# TalkingTrain.net
KiCad netlist of a schematic drawn in EasyEDA Pro
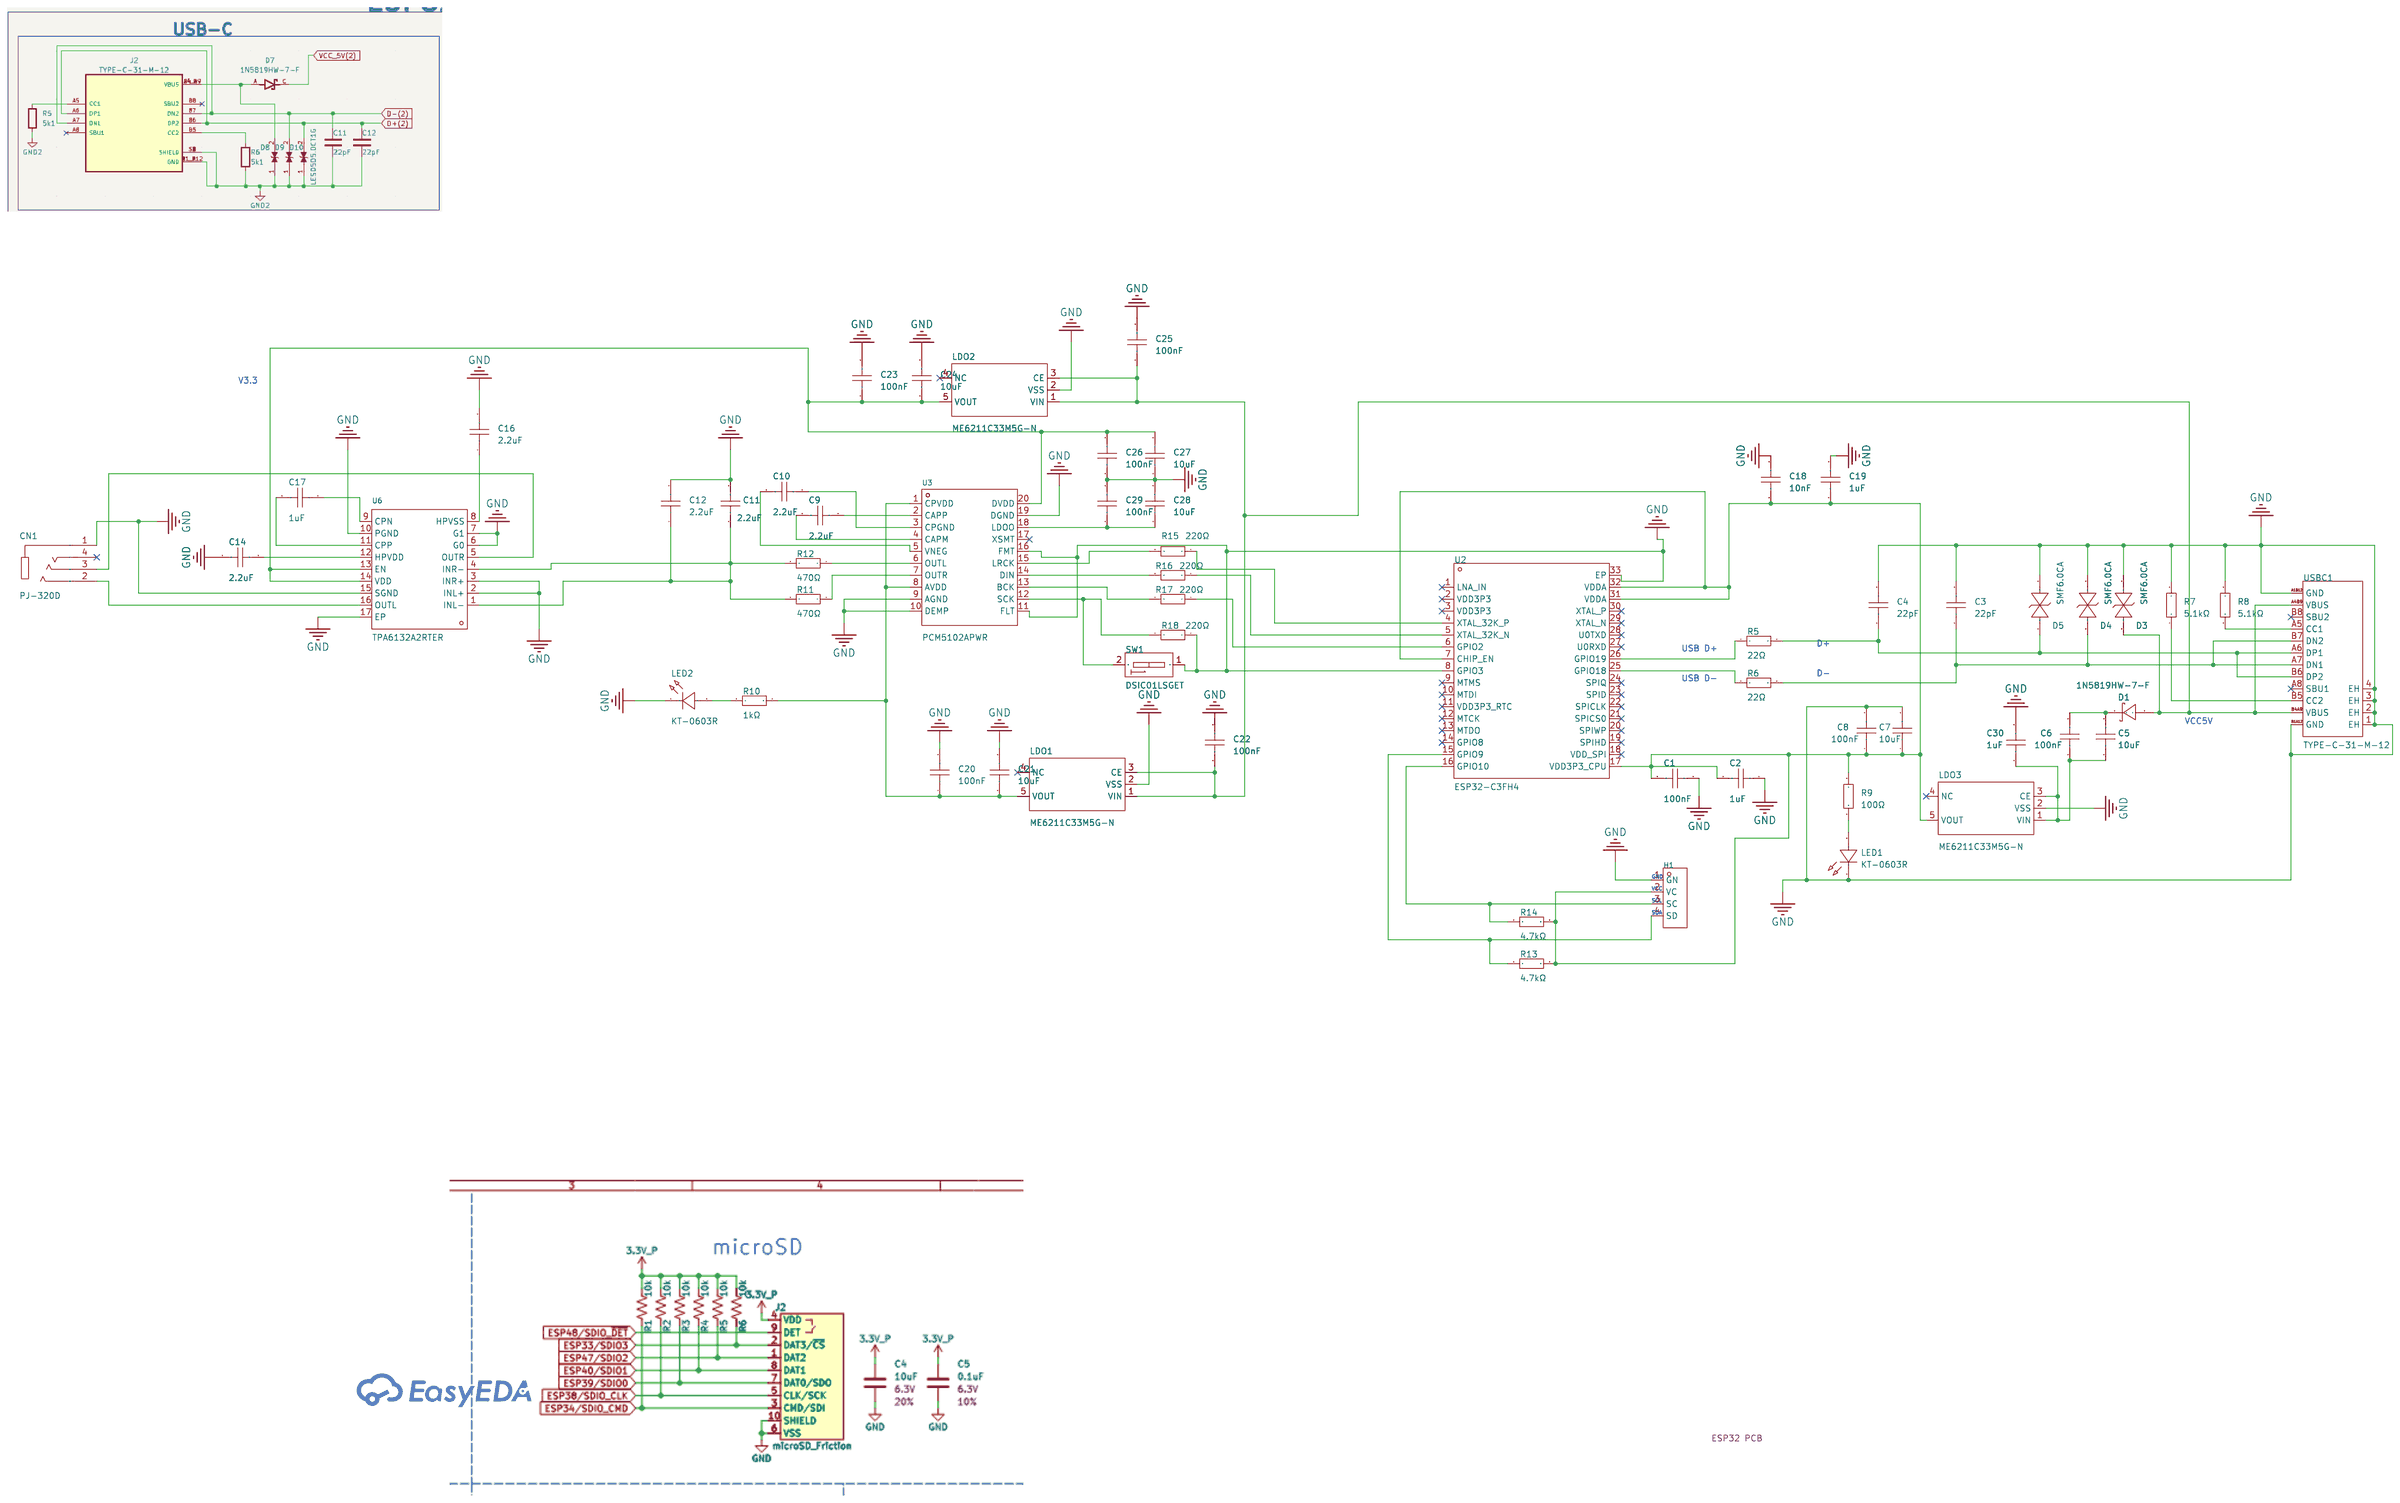
[diagram p0: schematic sheet]

(export (version "E")
  (design (tool "Eeschema 10.0.6"))
  (components
    (comp (ref "C1")
      (value "100nF")
      (footprint "easyedapro:C0603")
      (description "Capacitance:100nF Tolerance:±10% Tolerance:±10% Voltage Rating:50V Temperature Coefficient:X7R")
      (fields
        (field (name "Manufacturer Part") "CC0603KRX7R9BB104")
        (field (name "Manufacturer") "YAGEO(国巨)")
      )
      (libsource (lib "easyedapro") (part "CAP"))
    )
    (comp (ref "C2")
      (value "1uF")
      (footprint "easyedapro:C0603")
      (description "Capacitance:1uF Tolerance:±10% Tolerance:±10% Voltage Rating:50V Temperature Coefficient:X5R")
      (fields
        (field (name "Manufacturer Part") "CL10A105KB8NNNC")
        (field (name "Manufacturer") "SAMSUNG(三星)")
      )
      (libsource (lib "easyedapro") (part "CAP"))
    )
    (comp (ref "C3")
      (value "22pF")
      (footprint "easyedapro:C0603")
      (description "Capacitance:22pF Tolerance:±5% Tolerance:±5% Voltage Rating:50V Temperature Coefficient:C0G")
      (fields
        (field (name "Manufacturer Part") "CL10C220JB8NNNC")
        (field (name "Manufacturer") "SAMSUNG(三星)")
      )
      (libsource (lib "easyedapro") (part "CAP"))
    )
    (comp (ref "C4")
      (value "22pF")
      (footprint "easyedapro:C0603")
      (description "Capacitance:22pF Tolerance:±5% Tolerance:±5% Voltage Rating:50V Temperature Coefficient:C0G")
      (fields
        (field (name "Manufacturer Part") "CL10C220JB8NNNC")
        (field (name "Manufacturer") "SAMSUNG(三星)")
      )
      (libsource (lib "easyedapro") (part "CAP"))
    )
    (comp (ref "C5")
      (value "10uF")
      (footprint "easyedapro:C0603")
      (description "Capacitance:10uF Tolerance:±10% Tolerance:±10% Voltage Rating:10V Temperature Coefficient:X5R")
      (fields
        (field (name "Manufacturer Part") "CL10A106KP8NNNC")
        (field (name "Manufacturer") "SAMSUNG(三星)")
      )
      (libsource (lib "easyedapro") (part "CAP"))
    )
    (comp (ref "C6")
      (value "100nF")
      (footprint "easyedapro:C0603")
      (description "Capacitance:100nF Tolerance:±10% Tolerance:±10% Voltage Rating:50V Temperature Coefficient:X7R")
      (fields
        (field (name "Manufacturer Part") "CC0603KRX7R9BB104")
        (field (name "Manufacturer") "YAGEO(国巨)")
      )
      (libsource (lib "easyedapro") (part "CAP"))
    )
    (comp (ref "C7")
      (value "10uF")
      (footprint "easyedapro:C0603")
      (description "Capacitance:10uF Tolerance:±10% Tolerance:±10% Voltage Rating:10V Temperature Coefficient:X5R")
      (fields
        (field (name "Manufacturer Part") "CL10A106KP8NNNC")
        (field (name "Manufacturer") "SAMSUNG(三星)")
      )
      (libsource (lib "easyedapro") (part "CAP"))
    )
    (comp (ref "C8")
      (value "100nF")
      (footprint "easyedapro:C0603")
      (description "Capacitance:100nF Tolerance:±10% Tolerance:±10% Voltage Rating:50V Temperature Coefficient:X7R")
      (fields
        (field (name "Manufacturer Part") "CC0603KRX7R9BB104")
        (field (name "Manufacturer") "YAGEO(国巨)")
      )
      (libsource (lib "easyedapro") (part "CAP"))
    )
    (comp (ref "C9")
      (value "2.2uF")
      (footprint "easyedapro:C0603")
      (description "Capacitance:2.2uF Tolerance:±10% Tolerance:±10% Voltage Rating:16V Temperature Coefficient:X5R")
      (fields
        (field (name "Manufacturer Part") "CL10A225KO8NNNC")
        (field (name "Manufacturer") "SAMSUNG(三星)")
      )
      (libsource (lib "easyedapro") (part "CAP"))
    )
    (comp (ref "C10")
      (value "2.2uF")
      (footprint "easyedapro:C0603")
      (description "Capacitance:2.2uF Tolerance:±10% Tolerance:±10% Voltage Rating:16V Temperature Coefficient:X5R")
      (fields
        (field (name "Manufacturer Part") "CL10A225KO8NNNC")
        (field (name "Manufacturer") "SAMSUNG(三星)")
      )
      (libsource (lib "easyedapro") (part "CAP"))
    )
    (comp (ref "C11")
      (value "2.2uF")
      (footprint "easyedapro:C0603")
      (description "Capacitance:2.2uF Tolerance:±10% Tolerance:±10% Voltage Rating:16V Temperature Coefficient:X5R")
      (fields
        (field (name "Manufacturer Part") "CL10A225KO8NNNC")
        (field (name "Manufacturer") "SAMSUNG(三星)")
      )
      (libsource (lib "easyedapro") (part "CAP"))
    )
    (comp (ref "C12")
      (value "2.2uF")
      (footprint "easyedapro:C0603")
      (description "Capacitance:2.2uF Tolerance:±10% Tolerance:±10% Voltage Rating:16V Temperature Coefficient:X5R")
      (fields
        (field (name "Manufacturer Part") "CL10A225KO8NNNC")
        (field (name "Manufacturer") "SAMSUNG(三星)")
      )
      (libsource (lib "easyedapro") (part "CAP"))
    )
    (comp (ref "C14")
      (value "2.2uF")
      (footprint "easyedapro:C0603")
      (description "Capacitance:2.2uF Tolerance:±10% Tolerance:±10% Voltage Rating:16V Temperature Coefficient:X5R")
      (fields
        (field (name "Manufacturer Part") "CL10A225KO8NNNC")
        (field (name "Manufacturer") "SAMSUNG(三星)")
      )
      (libsource (lib "easyedapro") (part "CAP"))
    )
    (comp (ref "C16")
      (value "2.2uF")
      (footprint "easyedapro:C0603")
      (description "Capacitance:2.2uF Tolerance:±10% Tolerance:±10% Voltage Rating:16V Temperature Coefficient:X5R")
      (fields
        (field (name "Manufacturer Part") "CL10A225KO8NNNC")
        (field (name "Manufacturer") "SAMSUNG(三星)")
      )
      (libsource (lib "easyedapro") (part "CAP"))
    )
    (comp (ref "C17")
      (value "1uF")
      (footprint "easyedapro:C0603")
      (description "Capacitance:1uF Tolerance:±10% Tolerance:±10% Voltage Rating:50V Temperature Coefficient:X5R")
      (fields
        (field (name "Manufacturer Part") "CL10A105KB8NNNC")
        (field (name "Manufacturer") "SAMSUNG(三星)")
      )
      (libsource (lib "easyedapro") (part "CAP"))
    )
    (comp (ref "C18")
      (value "10nF")
      (footprint "easyedapro:C0603")
      (description "Capacitance:10nF Tolerance:±10% Tolerance:±10% Voltage Rating:50V Temperature Coefficient:X7R")
      (fields (field (name "Manufacturer Part") "0603B103K500NT") (field (name "Manufacturer") "FH(风华)"))
      (libsource (lib "easyedapro") (part "CAP"))
    )
    (comp (ref "C19")
      (value "1uF")
      (footprint "easyedapro:C0603")
      (description "Capacitance:1uF Tolerance:±10% Tolerance:±10% Voltage Rating:50V Temperature Coefficient:X5R")
      (fields
        (field (name "Manufacturer Part") "CL10A105KB8NNNC")
        (field (name "Manufacturer") "SAMSUNG(三星)")
      )
      (libsource (lib "easyedapro") (part "CAP"))
    )
    (comp (ref "C20")
      (value "100nF")
      (footprint "easyedapro:C0603")
      (description "Capacitance:100nF Tolerance:±10% Tolerance:±10% Voltage Rating:50V Temperature Coefficient:X7R")
      (fields
        (field (name "Manufacturer Part") "CC0603KRX7R9BB104")
        (field (name "Manufacturer") "YAGEO(国巨)")
      )
      (libsource (lib "easyedapro") (part "CAP"))
    )
    (comp (ref "C21")
      (value "10uF")
      (footprint "easyedapro:C0603")
      (description "Capacitance:10uF Tolerance:±10% Tolerance:±10% Voltage Rating:10V Temperature Coefficient:X5R")
      (fields
        (field (name "Manufacturer Part") "CL10A106KP8NNNC")
        (field (name "Manufacturer") "SAMSUNG(三星)")
      )
      (libsource (lib "easyedapro") (part "CAP"))
    )
    (comp (ref "C22")
      (value "100nF")
      (footprint "easyedapro:C0603")
      (description "Capacitance:100nF Tolerance:±10% Tolerance:±10% Voltage Rating:50V Temperature Coefficient:X7R")
      (fields
        (field (name "Manufacturer Part") "CC0603KRX7R9BB104")
        (field (name "Manufacturer") "YAGEO(国巨)")
      )
      (libsource (lib "easyedapro") (part "CAP"))
    )
    (comp (ref "C23")
      (value "100nF")
      (footprint "easyedapro:C0603")
      (description "Capacitance:100nF Tolerance:±10% Tolerance:±10% Voltage Rating:50V Temperature Coefficient:X7R")
      (fields
        (field (name "Manufacturer Part") "CC0603KRX7R9BB104")
        (field (name "Manufacturer") "YAGEO(国巨)")
      )
      (libsource (lib "easyedapro") (part "CAP"))
    )
    (comp (ref "C24")
      (value "10uF")
      (footprint "easyedapro:C0603")
      (description "Capacitance:10uF Tolerance:±10% Tolerance:±10% Voltage Rating:10V Temperature Coefficient:X5R")
      (fields
        (field (name "Manufacturer Part") "CL10A106KP8NNNC")
        (field (name "Manufacturer") "SAMSUNG(三星)")
      )
      (libsource (lib "easyedapro") (part "CAP"))
    )
    (comp (ref "C25")
      (value "100nF")
      (footprint "easyedapro:C0603")
      (description "Capacitance:100nF Tolerance:±10% Tolerance:±10% Voltage Rating:50V Temperature Coefficient:X7R")
      (fields
        (field (name "Manufacturer Part") "CC0603KRX7R9BB104")
        (field (name "Manufacturer") "YAGEO(国巨)")
      )
      (libsource (lib "easyedapro") (part "CAP"))
    )
    (comp (ref "C26")
      (value "100nF")
      (footprint "easyedapro:C0603")
      (description "Capacitance:100nF Tolerance:±10% Tolerance:±10% Voltage Rating:50V Temperature Coefficient:X7R")
      (fields
        (field (name "Manufacturer Part") "CC0603KRX7R9BB104")
        (field (name "Manufacturer") "YAGEO(国巨)")
      )
      (libsource (lib "easyedapro") (part "CAP"))
    )
    (comp (ref "C27")
      (value "10uF")
      (footprint "easyedapro:C0603")
      (description "Capacitance:10uF Tolerance:±10% Tolerance:±10% Voltage Rating:10V Temperature Coefficient:X5R")
      (fields
        (field (name "Manufacturer Part") "CL10A106KP8NNNC")
        (field (name "Manufacturer") "SAMSUNG(三星)")
      )
      (libsource (lib "easyedapro") (part "CAP"))
    )
    (comp (ref "C28")
      (value "10uF")
      (footprint "easyedapro:C0603")
      (description "Capacitance:10uF Tolerance:±10% Tolerance:±10% Voltage Rating:10V Temperature Coefficient:X5R")
      (fields
        (field (name "Manufacturer Part") "CL10A106KP8NNNC")
        (field (name "Manufacturer") "SAMSUNG(三星)")
      )
      (libsource (lib "easyedapro") (part "CAP"))
    )
    (comp (ref "C29")
      (value "100nF")
      (footprint "easyedapro:C0603")
      (description "Capacitance:100nF Tolerance:±10% Tolerance:±10% Voltage Rating:50V Temperature Coefficient:X7R")
      (fields
        (field (name "Manufacturer Part") "CC0603KRX7R9BB104")
        (field (name "Manufacturer") "YAGEO(国巨)")
      )
      (libsource (lib "easyedapro") (part "CAP"))
    )
    (comp (ref "C30")
      (value "1uF")
      (footprint "easyedapro:C0603")
      (description "Capacitance:1uF Tolerance:±10% Tolerance:±10% Voltage Rating:50V Temperature Coefficient:X7R")
      (fields
        (field (name "Manufacturer Part") "CL31B105KBHNNNE")
        (field (name "Manufacturer") "SAMSUNG(三星)")
      )
      (libsource (lib "easyedapro") (part "CAP"))
    )
    (comp (ref "CN1")
      (value "PJ-320D")
      (footprint "easyedapro:AUDIO-SMD_PJ-320D-1")
      (fields (field (name "Manufacturer") "SHOU HAN(首韩)"))
      (libsource (lib "easyedapro") (part "PJ-320D"))
    )
    (comp (ref "D1")
      (value "1N5819HW-7-F")
      (footprint "easyedapro:SOD-123_L2.7-W1.6-LS3.7-RD")
      (fields (field (name "Manufacturer") "DIODES(美台)"))
      (libsource (lib "easyedapro") (part "1N5819HW-7-F"))
    )
    (comp (ref "D3")
      (value "SMF6.0CA")
      (footprint "easyedapro:SOD-123FL_L2.7-W1.8-LS3.8-BI")
      (fields (field (name "Manufacturer") "R+O(宏嘉诚)"))
      (libsource (lib "easyedapro") (part "SMF6.0CA_C19077500"))
    )
    (comp (ref "D4")
      (value "SMF6.0CA")
      (footprint "easyedapro:SOD-123FL_L2.7-W1.8-LS3.8-BI")
      (fields (field (name "Manufacturer") "R+O(宏嘉诚)"))
      (libsource (lib "easyedapro") (part "SMF6.0CA_C19077500"))
    )
    (comp (ref "D5")
      (value "SMF6.0CA")
      (footprint "easyedapro:SOD-123FL_L2.7-W1.8-LS3.8-BI")
      (fields (field (name "Manufacturer") "R+O(宏嘉诚)"))
      (libsource (lib "easyedapro") (part "SMF6.0CA_C19077500"))
    )
    (comp (ref "H1")
      (value "2.54-1*4P母")
      (footprint "easyedapro:HDR-TH_4P-P2.54-V-F")
      (fields (field (name "Manufacturer") "BOOMELE(博穆精密)"))
      (libsource (lib "easyedapro") (part "2.54-1*4P母"))
    )
    (comp (ref "LDO1")
      (value "ME6211C33M5G-N")
      (footprint "easyedapro:SOT-23-5_L3.0-W1.7-P0.95-LS2.8-BL")
      (fields (field (name "Manufacturer") "MICRONE(南京微盟)"))
      (libsource (lib "easyedapro") (part "ME6211C33M5G-N"))
    )
    (comp (ref "LDO2")
      (value "ME6211C33M5G-N")
      (footprint "easyedapro:SOT-23-5_L3.0-W1.7-P0.95-LS2.8-BL")
      (fields (field (name "Manufacturer") "MICRONE(南京微盟)"))
      (libsource (lib "easyedapro") (part "ME6211C33M5G-N"))
    )
    (comp (ref "LDO3")
      (value "ME6211C33M5G-N")
      (footprint "easyedapro:SOT-23-5_L3.0-W1.7-P0.95-LS2.8-BL")
      (fields (field (name "Manufacturer") "MICRONE(南京微盟)"))
      (libsource (lib "easyedapro") (part "ME6211C33M5G-N"))
    )
    (comp (ref "LED1")
      (value "KT-0603R")
      (footprint "easyedapro:LED0603-RD_RED")
      (fields (field (name "Manufacturer") "KENTO"))
      (libsource (lib "easyedapro") (part "XL-1608SURC-06"))
    )
    (comp (ref "LED2")
      (value "KT-0603R")
      (footprint "easyedapro:LED0603-RD_RED")
      (fields (field (name "Manufacturer") "KENTO"))
      (libsource (lib "easyedapro") (part "XL-1608SURC-06"))
    )
    (comp (ref "R5")
      (value "22Ω")
      (footprint "easyedapro:R0603")
      (fields
        (field (name "Manufacturer Part") "0603WAF220JT5E")
        (field (name "Manufacturer") "UNI-ROYAL(厚声)")
      )
      (libsource (lib "easyedapro") (part "Res"))
    )
    (comp (ref "R6")
      (value "22Ω")
      (footprint "easyedapro:R0603")
      (fields
        (field (name "Manufacturer Part") "0603WAF220JT5E")
        (field (name "Manufacturer") "UNI-ROYAL(厚声)")
      )
      (libsource (lib "easyedapro") (part "Res"))
    )
    (comp (ref "R7")
      (value "5.1kΩ")
      (footprint "easyedapro:R0603")
      (fields
        (field (name "Manufacturer Part") "0805W8F5101T5E")
        (field (name "Manufacturer") "UNI-ROYAL(厚声)")
      )
      (libsource (lib "easyedapro") (part "Res"))
    )
    (comp (ref "R8")
      (value "5.1kΩ")
      (footprint "easyedapro:R0603")
      (fields
        (field (name "Manufacturer Part") "0805W8F5101T5E")
        (field (name "Manufacturer") "UNI-ROYAL(厚声)")
      )
      (libsource (lib "easyedapro") (part "Res"))
    )
    (comp (ref "R9")
      (value "100Ω")
      (footprint "easyedapro:R0603")
      (fields
        (field (name "Manufacturer Part") "0603WAF1000T5E")
        (field (name "Manufacturer") "UNI-ROYAL(厚声)")
      )
      (libsource (lib "easyedapro") (part "Res"))
    )
    (comp (ref "R10")
      (value "1kΩ")
      (footprint "easyedapro:R0603")
      (fields
        (field (name "Manufacturer Part") "0603WAF1001T5E")
        (field (name "Manufacturer") "UNI-ROYAL(厚声)")
      )
      (libsource (lib "easyedapro") (part "Res"))
    )
    (comp (ref "R11")
      (value "470Ω")
      (footprint "easyedapro:R0603")
      (fields
        (field (name "Manufacturer Part") "0603WAF4700T5E")
        (field (name "Manufacturer") "UNI-ROYAL(厚声)")
      )
      (libsource (lib "easyedapro") (part "Res"))
    )
    (comp (ref "R12")
      (value "470Ω")
      (footprint "easyedapro:R0603")
      (fields
        (field (name "Manufacturer Part") "0603WAF4700T5E")
        (field (name "Manufacturer") "UNI-ROYAL(厚声)")
      )
      (libsource (lib "easyedapro") (part "Res"))
    )
    (comp (ref "R13")
      (value "4.7kΩ")
      (footprint "easyedapro:R0603")
      (fields
        (field (name "Manufacturer Part") "0603WAF4701T5E")
        (field (name "Manufacturer") "UNI-ROYAL(厚声)")
      )
      (libsource (lib "easyedapro") (part "Res"))
    )
    (comp (ref "R14")
      (value "4.7kΩ")
      (footprint "easyedapro:R0603")
      (fields
        (field (name "Manufacturer Part") "0603WAF4701T5E")
        (field (name "Manufacturer") "UNI-ROYAL(厚声)")
      )
      (libsource (lib "easyedapro") (part "Res"))
    )
    (comp (ref "R15")
      (value "220Ω")
      (footprint "easyedapro:R0603")
      (fields
        (field (name "Manufacturer Part") "0603WAF2200T5E")
        (field (name "Manufacturer") "UNI-ROYAL(厚声)")
      )
      (libsource (lib "easyedapro") (part "Res"))
    )
    (comp (ref "R16")
      (value "220Ω")
      (footprint "easyedapro:R0603")
      (fields
        (field (name "Manufacturer Part") "0603WAF2200T5E")
        (field (name "Manufacturer") "UNI-ROYAL(厚声)")
      )
      (libsource (lib "easyedapro") (part "Res"))
    )
    (comp (ref "R17")
      (value "220Ω")
      (footprint "easyedapro:R0603")
      (fields
        (field (name "Manufacturer Part") "0603WAF2200T5E")
        (field (name "Manufacturer") "UNI-ROYAL(厚声)")
      )
      (libsource (lib "easyedapro") (part "Res"))
    )
    (comp (ref "R18")
      (value "220Ω")
      (footprint "easyedapro:R0603")
      (fields
        (field (name "Manufacturer Part") "0603WAF2200T5E")
        (field (name "Manufacturer") "UNI-ROYAL(厚声)")
      )
      (libsource (lib "easyedapro") (part "Res"))
    )
    (comp (ref "SW1")
      (value "DSIC01LSGET")
      (footprint "easyedapro:SW-SMD_DSIC01LSGET")
      (description "Type:Slide, Rocked Circuit:SPST Number of Positions:1 Lead Pitch:- Operating Life:- Color:Black")
      (fields (field (name "Manufacturer") "YE"))
      (libsource (lib "easyedapro") (part "DSIC01LSGET"))
    )
    (comp (ref "U2")
      (value "ESP32-C3FH4")
      (footprint "easyedapro:QFN-32_L5.0-W5.0-P0.50-TL-EP3.7")
      (fields (field (name "Manufacturer") "ESPRESSIF(乐鑫)"))
      (libsource (lib "easyedapro") (part "ESP32-C3FH4"))
    )
    (comp (ref "U3")
      (value "PCM5102APWR")
      (footprint "easyedapro:TSSOP-20_L6.5-W4.4-P0.65-LS6.4-BL")
      (fields (field (name "Manufacturer") "TI(德州仪器)"))
      (libsource (lib "easyedapro") (part "PCM5102APWR"))
    )
    (comp (ref "U6")
      (value "TPA6132A2RTER")
      (footprint "easyedapro:WQFN-16_L3.0-W3.0-P0.50-TL-EP1.6")
      (fields (field (name "Manufacturer") "TI(德州仪器)"))
      (libsource (lib "easyedapro") (part "TPA6132A2RTER"))
    )
    (comp (ref "USBC1")
      (value "TYPE-C-31-M-12")
      (footprint "easyedapro:USB-C_SMD-TYPE-C-31-M-12_1")
      (fields (field (name "Manufacturer") "韩国韩荣"))
      (libsource (lib "easyedapro") (part "TYPE-C-31-M-12"))
    )
  )
  (nets
    (net (code "1") (name "GND") (class "Default")
      (node (ref "C1") (pin "1") (pinfunction "1_1") (pintype "input"))
      (node (ref "C11") (pin "2") (pinfunction "2_2") (pintype "input"))
      (node (ref "C12") (pin "2") (pinfunction "2_2") (pintype "input"))
      (node (ref "C14") (pin "1") (pinfunction "1_1") (pintype "input"))
      (node (ref "C16") (pin "2") (pinfunction "2_2") (pintype "input"))
      (node (ref "C18") (pin "1") (pinfunction "1_1") (pintype "input"))
      (node (ref "C19") (pin "1") (pinfunction "1_1") (pintype "input"))
      (node (ref "C2") (pin "1") (pinfunction "1_1") (pintype "input"))
      (node (ref "C20") (pin "2") (pinfunction "2_2") (pintype "input"))
      (node (ref "C21") (pin "2") (pinfunction "2_2") (pintype "input"))
      (node (ref "C22") (pin "2") (pinfunction "2_2") (pintype "input"))
      (node (ref "C23") (pin "2") (pinfunction "2_2") (pintype "input"))
      (node (ref "C24") (pin "2") (pinfunction "2_2") (pintype "input"))
      (node (ref "C25") (pin "2") (pinfunction "2_2") (pintype "input"))
      (node (ref "C26") (pin "1") (pinfunction "1_1") (pintype "input"))
      (node (ref "C27") (pin "1") (pinfunction "1_1") (pintype "input"))
      (node (ref "C28") (pin "2") (pinfunction "2_2") (pintype "input"))
      (node (ref "C29") (pin "2") (pinfunction "2_2") (pintype "input"))
      (node (ref "C3") (pin "2") (pinfunction "2_2") (pintype "input"))
      (node (ref "C30") (pin "2") (pinfunction "2_2") (pintype "input"))
      (node (ref "C4") (pin "2") (pinfunction "2_2") (pintype "input"))
      (node (ref "C7") (pin "2") (pinfunction "2_2") (pintype "input"))
      (node (ref "C8") (pin "2") (pinfunction "2_2") (pintype "input"))
      (node (ref "CN1") (pin "1") (pinfunction "1_1") (pintype "unspecified"))
      (node (ref "D3") (pin "1") (pinfunction "1_1") (pintype "unspecified"))
      (node (ref "D4") (pin "1") (pinfunction "1_1") (pintype "unspecified"))
      (node (ref "D5") (pin "1") (pinfunction "1_1") (pintype "unspecified"))
      (node (ref "H1") (pin "1") (pinfunction "GN_1") (pintype "input"))
      (node (ref "LDO1") (pin "2") (pinfunction "VSS_2") (pintype "unspecified"))
      (node (ref "LDO2") (pin "2") (pinfunction "VSS_2") (pintype "unspecified"))
      (node (ref "LDO3") (pin "2") (pinfunction "VSS_2") (pintype "unspecified"))
      (node (ref "LED1") (pin "1") (pinfunction "K_1") (pintype "unspecified"))
      (node (ref "LED2") (pin "1") (pinfunction "K_1") (pintype "unspecified"))
      (node (ref "R18") (pin "1") (pinfunction "1_1") (pintype "input"))
      (node (ref "R7") (pin "2") (pinfunction "2_2") (pintype "input"))
      (node (ref "R8") (pin "2") (pinfunction "2_2") (pintype "input"))
      (node (ref "SW1") (pin "1") (pinfunction "A1_1") (pintype "input"))
      (node (ref "U2") (pin "33") (pinfunction "EP_33") (pintype "unspecified"))
      (node (ref "U2") (pin "8") (pinfunction "GPIO3_8") (pintype "unspecified"))
      (node (ref "U3") (pin "10") (pinfunction "DEMP_10") (pintype "input"))
      (node (ref "U3") (pin "11") (pinfunction "FLT_11") (pintype "input"))
      (node (ref "U3") (pin "16") (pinfunction "FMT_16") (pintype "input"))
      (node (ref "U3") (pin "19") (pinfunction "DGND_19") (pintype "input"))
      (node (ref "U3") (pin "9") (pinfunction "AGND_9") (pintype "input"))
      (node (ref "U6") (pin "10") (pinfunction "PGND_10") (pintype "input"))
      (node (ref "U6") (pin "15") (pinfunction "SGND_15") (pintype "input"))
      (node (ref "U6") (pin "17") (pinfunction "EP_17") (pintype "input"))
      (node (ref "U6") (pin "2") (pinfunction "INL+_2") (pintype "input"))
      (node (ref "U6") (pin "3") (pinfunction "INR+_3") (pintype "input"))
      (node (ref "U6") (pin "6") (pinfunction "G0_6") (pintype "input"))
      (node (ref "U6") (pin "7") (pinfunction "G1_7") (pintype "input"))
      (node (ref "USBC1") (pin "1") (pinfunction "EH_1") (pintype "unspecified"))
      (node (ref "USBC1") (pin "2") (pinfunction "EH_2") (pintype "unspecified"))
      (node (ref "USBC1") (pin "3") (pinfunction "EH_3") (pintype "unspecified"))
      (node (ref "USBC1") (pin "4") (pinfunction "EH_4") (pintype "unspecified"))
      (node (ref "USBC1") (pin "A1B12") (pinfunction "GND_A1B12") (pintype "unspecified"))
      (node (ref "USBC1") (pin "B1A12") (pinfunction "GND_B1A12") (pintype "unspecified"))
    )
    (net (code "2") (name "Net-(D1-A)") (class "Default")
      (node (ref "C22") (pin "1") (pinfunction "1_1") (pintype "input"))
      (node (ref "C25") (pin "1") (pinfunction "1_1") (pintype "input"))
      (node (ref "D1") (pin "2") (pinfunction "A_2") (pintype "unspecified"))
      (node (ref "D3") (pin "2") (pinfunction "2_2") (pintype "unspecified"))
      (node (ref "LDO1") (pin "1") (pinfunction "VIN_1") (pintype "unspecified"))
      (node (ref "LDO1") (pin "3") (pinfunction "CE_3") (pintype "unspecified"))
      (node (ref "LDO2") (pin "1") (pinfunction "VIN_1") (pintype "unspecified"))
      (node (ref "LDO2") (pin "3") (pinfunction "CE_3") (pintype "unspecified"))
      (node (ref "USBC1") (pin "A4B9") (pinfunction "VBUS_A4B9") (pintype "unspecified"))
      (node (ref "USBC1") (pin "B4A9") (pinfunction "VBUS_B4A9") (pintype "unspecified"))
    )
    (net (code "3") (name "Net-(D1-K)") (class "Default")
      (node (ref "C5") (pin "2") (pinfunction "2_2") (pintype "input"))
      (node (ref "C6") (pin "2") (pinfunction "2_2") (pintype "input"))
      (node (ref "D1") (pin "1") (pinfunction "K_1") (pintype "unspecified"))
    )
    (net (code "4") (name "Net-(H1-SC)") (class "Default")
      (node (ref "H1") (pin "3") (pinfunction "SC_3") (pintype "input"))
      (node (ref "R14") (pin "1") (pinfunction "1_1") (pintype "input"))
      (node (ref "U2") (pin "16") (pinfunction "GPIO10_16") (pintype "unspecified"))
    )
    (net (code "5") (name "Net-(H1-SD)") (class "Default")
      (node (ref "H1") (pin "4") (pinfunction "SD_4") (pintype "input"))
      (node (ref "R13") (pin "1") (pinfunction "1_1") (pintype "input"))
      (node (ref "U2") (pin "15") (pinfunction "GPIO9_15") (pintype "unspecified"))
    )
    (net (code "6") (name "Net-(H1-VC)") (class "Default")
      (node (ref "C1") (pin "2") (pinfunction "2_2") (pintype "input"))
      (node (ref "C18") (pin "2") (pinfunction "2_2") (pintype "input"))
      (node (ref "C19") (pin "2") (pinfunction "2_2") (pintype "input"))
      (node (ref "C2") (pin "2") (pinfunction "2_2") (pintype "input"))
      (node (ref "C7") (pin "1") (pinfunction "1_1") (pintype "input"))
      (node (ref "C8") (pin "1") (pinfunction "1_1") (pintype "input"))
      (node (ref "H1") (pin "2") (pinfunction "VC_2") (pintype "input"))
      (node (ref "LDO3") (pin "5") (pinfunction "VOUT_5") (pintype "unspecified"))
      (node (ref "R13") (pin "2") (pinfunction "2_2") (pintype "input"))
      (node (ref "R14") (pin "2") (pinfunction "2_2") (pintype "input"))
      (node (ref "R9") (pin "2") (pinfunction "2_2") (pintype "input"))
      (node (ref "U2") (pin "17") (pinfunction "VDD3P3_CPU_17") (pintype "unspecified"))
      (node (ref "U2") (pin "31") (pinfunction "VDDA_31") (pintype "unspecified"))
      (node (ref "U2") (pin "32") (pinfunction "VDDA_32") (pintype "unspecified"))
      (node (ref "U2") (pin "7") (pinfunction "CHIP_EN_7") (pintype "unspecified"))
    )
    (net (code "7") (name "Net-(LDO1-VOUT)") (class "Default")
      (node (ref "C20") (pin "1") (pinfunction "1_1") (pintype "input"))
      (node (ref "C21") (pin "1") (pinfunction "1_1") (pintype "input"))
      (node (ref "LDO1") (pin "5") (pinfunction "VOUT_5") (pintype "unspecified"))
      (node (ref "R10") (pin "1") (pinfunction "1_1") (pintype "input"))
      (node (ref "U3") (pin "1") (pinfunction "CPVDD_1") (pintype "input"))
      (node (ref "U3") (pin "8") (pinfunction "AVDD_8") (pintype "input"))
    )
    (net (code "8") (name "Net-(LDO2-VOUT)") (class "Default")
      (node (ref "C23") (pin "1") (pinfunction "1_1") (pintype "input"))
      (node (ref "C24") (pin "1") (pinfunction "1_1") (pintype "input"))
      (node (ref "C26") (pin "2") (pinfunction "2_2") (pintype "input"))
      (node (ref "C27") (pin "2") (pinfunction "2_2") (pintype "input"))
      (node (ref "LDO2") (pin "5") (pinfunction "VOUT_5") (pintype "unspecified"))
      (node (ref "U3") (pin "20") (pinfunction "DVDD_20") (pintype "input"))
      (node (ref "U6") (pin "13") (pinfunction "EN_13") (pintype "input"))
      (node (ref "U6") (pin "14") (pinfunction "VDD_14") (pintype "input"))
    )
    (net (code "9") (name "Net-(LDO3-CE)") (class "Default")
      (node (ref "C30") (pin "1") (pinfunction "1_1") (pintype "input"))
      (node (ref "C5") (pin "1") (pinfunction "1_1") (pintype "input"))
      (node (ref "C6") (pin "1") (pinfunction "1_1") (pintype "input"))
      (node (ref "LDO3") (pin "1") (pinfunction "VIN_1") (pintype "unspecified"))
      (node (ref "LDO3") (pin "3") (pinfunction "CE_3") (pintype "unspecified"))
    )
    (net (code "10") (name "Net-(LED1-A)") (class "Default")
      (node (ref "LED1") (pin "2") (pinfunction "A_2") (pintype "unspecified"))
      (node (ref "R9") (pin "1") (pinfunction "1_1") (pintype "input"))
    )
    (net (code "11") (name "Net-(LED2-A)") (class "Default")
      (node (ref "LED2") (pin "2") (pinfunction "A_2") (pintype "unspecified"))
      (node (ref "R10") (pin "2") (pinfunction "2_2") (pintype "input"))
    )
    (net (code "12") (name "Net-(SW1-A2)") (class "Default")
      (node (ref "R18") (pin "2") (pinfunction "2_2") (pintype "input"))
      (node (ref "SW1") (pin "2") (pinfunction "A2_2") (pintype "input"))
      (node (ref "U3") (pin "12") (pinfunction "SCK_12") (pintype "input"))
    )
    (net (code "13") (name "Net-(U2-GPIO2)") (class "Default")
      (node (ref "R17") (pin "1") (pinfunction "1_1") (pintype "input"))
      (node (ref "U2") (pin "6") (pinfunction "GPIO2_6") (pintype "unspecified"))
    )
    (net (code "14") (name "Net-(U2-GPIO18)") (class "Default")
      (node (ref "R6") (pin "1") (pinfunction "1_1") (pintype "input"))
      (node (ref "U2") (pin "25") (pinfunction "GPIO18_25") (pintype "unspecified"))
    )
    (net (code "15") (name "Net-(U2-GPIO19)") (class "Default")
      (node (ref "R5") (pin "1") (pinfunction "1_1") (pintype "input"))
      (node (ref "U2") (pin "26") (pinfunction "GPIO19_26") (pintype "unspecified"))
    )
    (net (code "16") (name "Net-(U2-XTAL_32K_N)") (class "Default")
      (node (ref "R16") (pin "1") (pinfunction "1_1") (pintype "input"))
      (node (ref "U2") (pin "5") (pinfunction "XTAL_32K_N_5") (pintype "unspecified"))
    )
    (net (code "17") (name "Net-(U2-XTAL_32K_P)") (class "Default")
      (node (ref "R15") (pin "1") (pinfunction "1_1") (pintype "input"))
      (node (ref "U2") (pin "4") (pinfunction "XTAL_32K_P_4") (pintype "unspecified"))
    )
    (net (code "18") (name "Net-(U3-BCK)") (class "Default")
      (node (ref "R17") (pin "2") (pinfunction "2_2") (pintype "input"))
      (node (ref "U3") (pin "13") (pinfunction "BCK_13") (pintype "input"))
    )
    (net (code "19") (name "Net-(U3-CAPM)") (class "Default")
      (node (ref "C9") (pin "2") (pinfunction "2_2") (pintype "input"))
      (node (ref "U3") (pin "4") (pinfunction "CAPM_4") (pintype "input"))
    )
    (net (code "20") (name "Net-(U3-CAPP)") (class "Default")
      (node (ref "C9") (pin "1") (pinfunction "1_1") (pintype "input"))
      (node (ref "U3") (pin "2") (pinfunction "CAPP_2") (pintype "input"))
    )
    (net (code "21") (name "Net-(U3-CPGND)") (class "Default")
      (node (ref "C10") (pin "1") (pinfunction "1_1") (pintype "input"))
      (node (ref "U3") (pin "3") (pinfunction "CPGND_3") (pintype "input"))
    )
    (net (code "22") (name "Net-(U3-DIN)") (class "Default")
      (node (ref "R16") (pin "2") (pinfunction "2_2") (pintype "input"))
      (node (ref "U3") (pin "14") (pinfunction "DIN_14") (pintype "input"))
    )
    (net (code "23") (name "Net-(U3-LDOO)") (class "Default")
      (node (ref "C28") (pin "1") (pinfunction "1_1") (pintype "input"))
      (node (ref "C29") (pin "1") (pinfunction "1_1") (pintype "input"))
      (node (ref "U3") (pin "18") (pinfunction "LDOO_18") (pintype "input"))
    )
    (net (code "24") (name "Net-(U3-LRCK)") (class "Default")
      (node (ref "R15") (pin "2") (pinfunction "2_2") (pintype "input"))
      (node (ref "U3") (pin "15") (pinfunction "LRCK_15") (pintype "input"))
    )
    (net (code "25") (name "Net-(U3-OUTL)") (class "Default")
      (node (ref "R12") (pin "1") (pinfunction "1_1") (pintype "input"))
      (node (ref "U3") (pin "6") (pinfunction "OUTL_6") (pintype "input"))
    )
    (net (code "26") (name "Net-(U3-OUTR)") (class "Default")
      (node (ref "R11") (pin "1") (pinfunction "1_1") (pintype "input"))
      (node (ref "U3") (pin "7") (pinfunction "OUTR_7") (pintype "input"))
    )
    (net (code "27") (name "Net-(U3-VNEG)") (class "Default")
      (node (ref "C10") (pin "2") (pinfunction "2_2") (pintype "input"))
      (node (ref "U3") (pin "5") (pinfunction "VNEG_5") (pintype "input"))
    )
    (net (code "28") (name "Net-(U6-CPN)") (class "Default")
      (node (ref "C17") (pin "1") (pinfunction "1_1") (pintype "input"))
      (node (ref "U6") (pin "9") (pinfunction "CPN_9") (pintype "input"))
    )
    (net (code "29") (name "Net-(U6-CPP)") (class "Default")
      (node (ref "C17") (pin "2") (pinfunction "2_2") (pintype "input"))
      (node (ref "U6") (pin "11") (pinfunction "CPP_11") (pintype "input"))
    )
    (net (code "30") (name "Net-(U6-HPVDD)") (class "Default")
      (node (ref "C14") (pin "2") (pinfunction "2_2") (pintype "input"))
      (node (ref "U6") (pin "12") (pinfunction "HPVDD_12") (pintype "input"))
    )
    (net (code "31") (name "Net-(U6-HPVSS)") (class "Default")
      (node (ref "C16") (pin "1") (pinfunction "1_1") (pintype "input"))
      (node (ref "U6") (pin "8") (pinfunction "HPVSS_8") (pintype "input"))
    )
    (net (code "32") (name "Net-(U6-INL-)") (class "Default")
      (node (ref "C11") (pin "1") (pinfunction "1_1") (pintype "input"))
      (node (ref "C12") (pin "1") (pinfunction "1_1") (pintype "input"))
      (node (ref "R11") (pin "2") (pinfunction "2_2") (pintype "input"))
      (node (ref "R12") (pin "2") (pinfunction "2_2") (pintype "input"))
      (node (ref "U6") (pin "1") (pinfunction "INL-_1") (pintype "input"))
      (node (ref "U6") (pin "4") (pinfunction "INR-_4") (pintype "input"))
    )
    (net (code "33") (name "Net-(U6-OUTL)") (class "Default")
      (node (ref "CN1") (pin "2") (pinfunction "2_2") (pintype "unspecified"))
      (node (ref "U6") (pin "16") (pinfunction "OUTL_16") (pintype "input"))
    )
    (net (code "34") (name "Net-(U6-OUTR)") (class "Default")
      (node (ref "CN1") (pin "3") (pinfunction "3_3") (pintype "unspecified"))
      (node (ref "U6") (pin "5") (pinfunction "OUTR_5") (pintype "input"))
    )
    (net (code "35") (name "Net-(USBC1-CC1)") (class "Default")
      (node (ref "R8") (pin "1") (pinfunction "1_1") (pintype "input"))
      (node (ref "USBC1") (pin "A5") (pinfunction "CC1_A5") (pintype "unspecified"))
    )
    (net (code "36") (name "Net-(USBC1-CC2)") (class "Default")
      (node (ref "R7") (pin "1") (pinfunction "1_1") (pintype "input"))
      (node (ref "USBC1") (pin "B5") (pinfunction "CC2_B5") (pintype "unspecified"))
    )
    (net (code "37") (name "Net-(USBC1-DN1)") (class "Default")
      (node (ref "C3") (pin "1") (pinfunction "1_1") (pintype "input"))
      (node (ref "D4") (pin "2") (pinfunction "2_2") (pintype "unspecified"))
      (node (ref "R6") (pin "2") (pinfunction "2_2") (pintype "input"))
      (node (ref "USBC1") (pin "A7") (pinfunction "DN1_A7") (pintype "unspecified"))
      (node (ref "USBC1") (pin "B7") (pinfunction "DN2_B7") (pintype "unspecified"))
    )
    (net (code "38") (name "Net-(USBC1-DP1)") (class "Default")
      (node (ref "C4") (pin "1") (pinfunction "1_1") (pintype "input"))
      (node (ref "D5") (pin "2") (pinfunction "2_2") (pintype "unspecified"))
      (node (ref "R5") (pin "2") (pinfunction "2_2") (pintype "input"))
      (node (ref "USBC1") (pin "A6") (pinfunction "DP1_A6") (pintype "unspecified"))
      (node (ref "USBC1") (pin "B6") (pinfunction "DP2_B6") (pintype "unspecified"))
    )
    (net (code "39") (name "unconnected-(CN1-Pad4)") (class "Default")
      (node (ref "CN1") (pin "4") (pinfunction "4_4") (pintype "unspecified+no_connect"))
    )
    (net (code "40") (name "unconnected-(LDO1-NC-Pad4)") (class "Default")
      (node (ref "LDO1") (pin "4") (pinfunction "NC_4") (pintype "unspecified+no_connect"))
    )
    (net (code "41") (name "unconnected-(LDO2-NC-Pad4)") (class "Default")
      (node (ref "LDO2") (pin "4") (pinfunction "NC_4") (pintype "unspecified+no_connect"))
    )
    (net (code "42") (name "unconnected-(LDO3-NC-Pad4)") (class "Default")
      (node (ref "LDO3") (pin "4") (pinfunction "NC_4") (pintype "unspecified+no_connect"))
    )
    (net (code "43") (name "unconnected-(U2-GPIO8-Pad14)") (class "Default")
      (node (ref "U2") (pin "14") (pinfunction "GPIO8_14") (pintype "unspecified+no_connect"))
    )
    (net (code "44") (name "unconnected-(U2-LNA_IN-Pad1)") (class "Default")
      (node (ref "U2") (pin "1") (pinfunction "LNA_IN_1") (pintype "unspecified+no_connect"))
    )
    (net (code "45") (name "unconnected-(U2-MTCK-Pad12)") (class "Default")
      (node (ref "U2") (pin "12") (pinfunction "MTCK_12") (pintype "unspecified+no_connect"))
    )
    (net (code "46") (name "unconnected-(U2-MTDI-Pad10)") (class "Default")
      (node (ref "U2") (pin "10") (pinfunction "MTDI_10") (pintype "unspecified+no_connect"))
    )
    (net (code "47") (name "unconnected-(U2-MTDO-Pad13)") (class "Default")
      (node (ref "U2") (pin "13") (pinfunction "MTDO_13") (pintype "unspecified+no_connect"))
    )
    (net (code "48") (name "unconnected-(U2-MTMS-Pad9)") (class "Default")
      (node (ref "U2") (pin "9") (pinfunction "MTMS_9") (pintype "unspecified+no_connect"))
    )
    (net (code "49") (name "unconnected-(U2-SPICLK-Pad22)") (class "Default")
      (node (ref "U2") (pin "22") (pinfunction "SPICLK_22") (pintype "unspecified+no_connect"))
    )
    (net (code "50") (name "unconnected-(U2-SPICS0-Pad21)") (class "Default")
      (node (ref "U2") (pin "21") (pinfunction "SPICS0_21") (pintype "unspecified+no_connect"))
    )
    (net (code "51") (name "unconnected-(U2-SPID-Pad23)") (class "Default")
      (node (ref "U2") (pin "23") (pinfunction "SPID_23") (pintype "unspecified+no_connect"))
    )
    (net (code "52") (name "unconnected-(U2-SPIHD-Pad19)") (class "Default")
      (node (ref "U2") (pin "19") (pinfunction "SPIHD_19") (pintype "unspecified+no_connect"))
    )
    (net (code "53") (name "unconnected-(U2-SPIQ-Pad24)") (class "Default")
      (node (ref "U2") (pin "24") (pinfunction "SPIQ_24") (pintype "unspecified+no_connect"))
    )
    (net (code "54") (name "unconnected-(U2-SPIWP-Pad20)") (class "Default")
      (node (ref "U2") (pin "20") (pinfunction "SPIWP_20") (pintype "unspecified+no_connect"))
    )
    (net (code "55") (name "unconnected-(U2-U0RXD-Pad27)") (class "Default")
      (node (ref "U2") (pin "27") (pinfunction "U0RXD_27") (pintype "unspecified+no_connect"))
    )
    (net (code "56") (name "unconnected-(U2-U0TXD-Pad28)") (class "Default")
      (node (ref "U2") (pin "28") (pinfunction "U0TXD_28") (pintype "unspecified+no_connect"))
    )
    (net (code "57") (name "unconnected-(U2-VDD3P3-Pad2)") (class "Default")
      (node (ref "U2") (pin "2") (pinfunction "VDD3P3_2") (pintype "unspecified+no_connect"))
    )
    (net (code "58") (name "unconnected-(U2-VDD3P3-Pad3)") (class "Default")
      (node (ref "U2") (pin "3") (pinfunction "VDD3P3_3") (pintype "unspecified+no_connect"))
    )
    (net (code "59") (name "unconnected-(U2-VDD3P3_RTC-Pad11)") (class "Default")
      (node (ref "U2") (pin "11") (pinfunction "VDD3P3_RTC_11") (pintype "unspecified+no_connect"))
    )
    (net (code "60") (name "unconnected-(U2-VDD_SPI-Pad18)") (class "Default")
      (node (ref "U2") (pin "18") (pinfunction "VDD_SPI_18") (pintype "unspecified+no_connect"))
    )
    (net (code "61") (name "unconnected-(U2-XTAL_N-Pad29)") (class "Default")
      (node (ref "U2") (pin "29") (pinfunction "XTAL_N_29") (pintype "unspecified+no_connect"))
    )
    (net (code "62") (name "unconnected-(U2-XTAL_P-Pad30)") (class "Default")
      (node (ref "U2") (pin "30") (pinfunction "XTAL_P_30") (pintype "unspecified+no_connect"))
    )
    (net (code "63") (name "unconnected-(U3-XSMT-Pad17)") (class "Default")
      (node (ref "U3") (pin "17") (pinfunction "XSMT_17") (pintype "input+no_connect"))
    )
    (net (code "64") (name "unconnected-(USBC1-SBU1-PadA8)") (class "Default")
      (node (ref "USBC1") (pin "A8") (pinfunction "SBU1_A8") (pintype "unspecified+no_connect"))
    )
    (net (code "65") (name "unconnected-(USBC1-SBU2-PadB8)") (class "Default")
      (node (ref "USBC1") (pin "B8") (pinfunction "SBU2_B8") (pintype "unspecified+no_connect"))
    )
  )
)
